# power-12VAC-5DC-7805.net
KiCad netlist of a schematic drawn in EAGLE
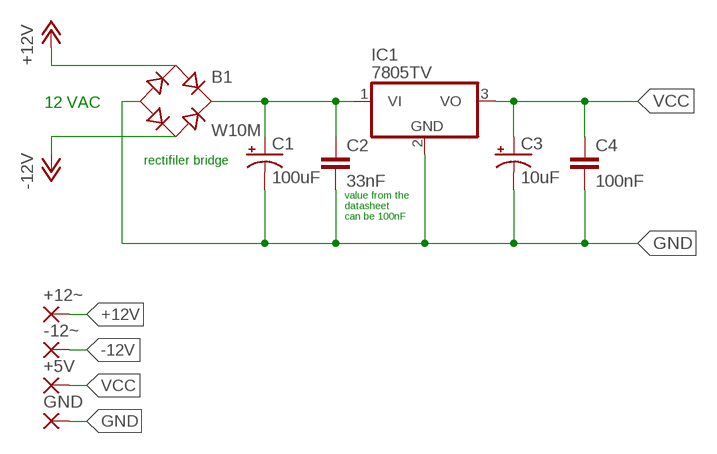
[diagram p0: schematic, sheet 1]

(export (version "E")
  (design (tool "Eeschema 10.0.6"))
  (components
    (comp (ref "+5V")
      (value "WIREPAD2,15/1,0")
      (footprint "eagle-import:2,15_1,0")
      (libsource (lib "eagle-import") (part "WIREPAD2,15/1,0"))
    )
    (comp (ref "+12~")
      (value "WIREPAD2,15/1,0")
      (footprint "eagle-import:2,15_1,0")
      (libsource (lib "eagle-import") (part "WIREPAD2,15/1,0"))
    )
    (comp (ref "-12~")
      (value "WIREPAD2,15/1,0")
      (footprint "eagle-import:2,15_1,0")
      (libsource (lib "eagle-import") (part "WIREPAD2,15/1,0"))
    )
    (comp (ref "B1")
      (value "W10M")
      (footprint "eagle-import:RB1A")
      (libsource (lib "eagle-import") (part "RB1A"))
    )
    (comp (ref "C1")
      (value "100uF")
      (footprint "eagle-import:CPOL-RADIAL-100UF-25V")
      (libsource (lib "eagle-import") (part "CAP_POLPTH1"))
    )
    (comp (ref "C2")
      (value "33nF")
      (footprint "eagle-import:CAP-PTH-SMALL")
      (libsource (lib "eagle-import") (part "CAPPTH"))
    )
    (comp (ref "C3")
      (value "10uF")
      (footprint "eagle-import:CPOL-RADIAL-100UF-25V")
      (libsource (lib "eagle-import") (part "CAP_POLPTH1"))
    )
    (comp (ref "C4")
      (value "100nF")
      (footprint "eagle-import:CAP-PTH-SMALL")
      (libsource (lib "eagle-import") (part "CAPPTH"))
    )
    (comp (ref "GND")
      (value "WIREPAD2,15/1,0")
      (footprint "eagle-import:2,15_1,0")
      (libsource (lib "eagle-import") (part "WIREPAD2,15/1,0"))
    )
    (comp (ref "IC1")
      (value "7805TV")
      (footprint "eagle-import:TO220V")
      (libsource (lib "eagle-import") (part "78TV05"))
    )
  )
  (nets
    (net (code "1") (name "+12V") (class "Default")
      (node (ref "+12~") (pin "1") (pinfunction "P_1") (pintype "passive"))
      (node (ref "B1") (pin "AC1") (pinfunction "AC1_AC1") (pintype "passive"))
    )
    (net (code "2") (name "-12V") (class "Default")
      (node (ref "-12~") (pin "1") (pinfunction "P_1") (pintype "passive"))
      (node (ref "B1") (pin "AC2") (pinfunction "AC2_AC2") (pintype "passive"))
    )
    (net (code "3") (name "GND") (class "Default")
      (node (ref "B1") (pin "-") (pinfunction "-_-") (pintype "passive"))
      (node (ref "C1") (pin "2") (pinfunction "-_2") (pintype "passive"))
      (node (ref "C2") (pin "2") (pinfunction "2_2") (pintype "passive"))
      (node (ref "C3") (pin "2") (pinfunction "-_2") (pintype "passive"))
      (node (ref "C4") (pin "2") (pinfunction "2_2") (pintype "passive"))
      (node (ref "GND") (pin "1") (pinfunction "P_1") (pintype "passive"))
      (node (ref "IC1") (pin "2") (pinfunction "GND_2") (pintype "passive"))
    )
    (net (code "4") (name "Net-(C1-+)") (class "Default")
      (node (ref "B1") (pin "+") (pinfunction "+_+") (pintype "passive"))
      (node (ref "C1") (pin "1") (pinfunction "+_1") (pintype "passive"))
      (node (ref "C2") (pin "1") (pinfunction "1_1") (pintype "passive"))
      (node (ref "IC1") (pin "1") (pinfunction "VI_1") (pintype "input"))
    )
    (net (code "5") (name "VCC") (class "Default")
      (node (ref "+5V") (pin "1") (pinfunction "P_1") (pintype "passive"))
      (node (ref "C3") (pin "1") (pinfunction "+_1") (pintype "passive"))
      (node (ref "C4") (pin "1") (pinfunction "1_1") (pintype "passive"))
      (node (ref "IC1") (pin "3") (pinfunction "VO_3") (pintype "passive"))
    )
  )
)
